# ADC_channel.net
KiCad netlist of a schematic drawn in Altium Designer
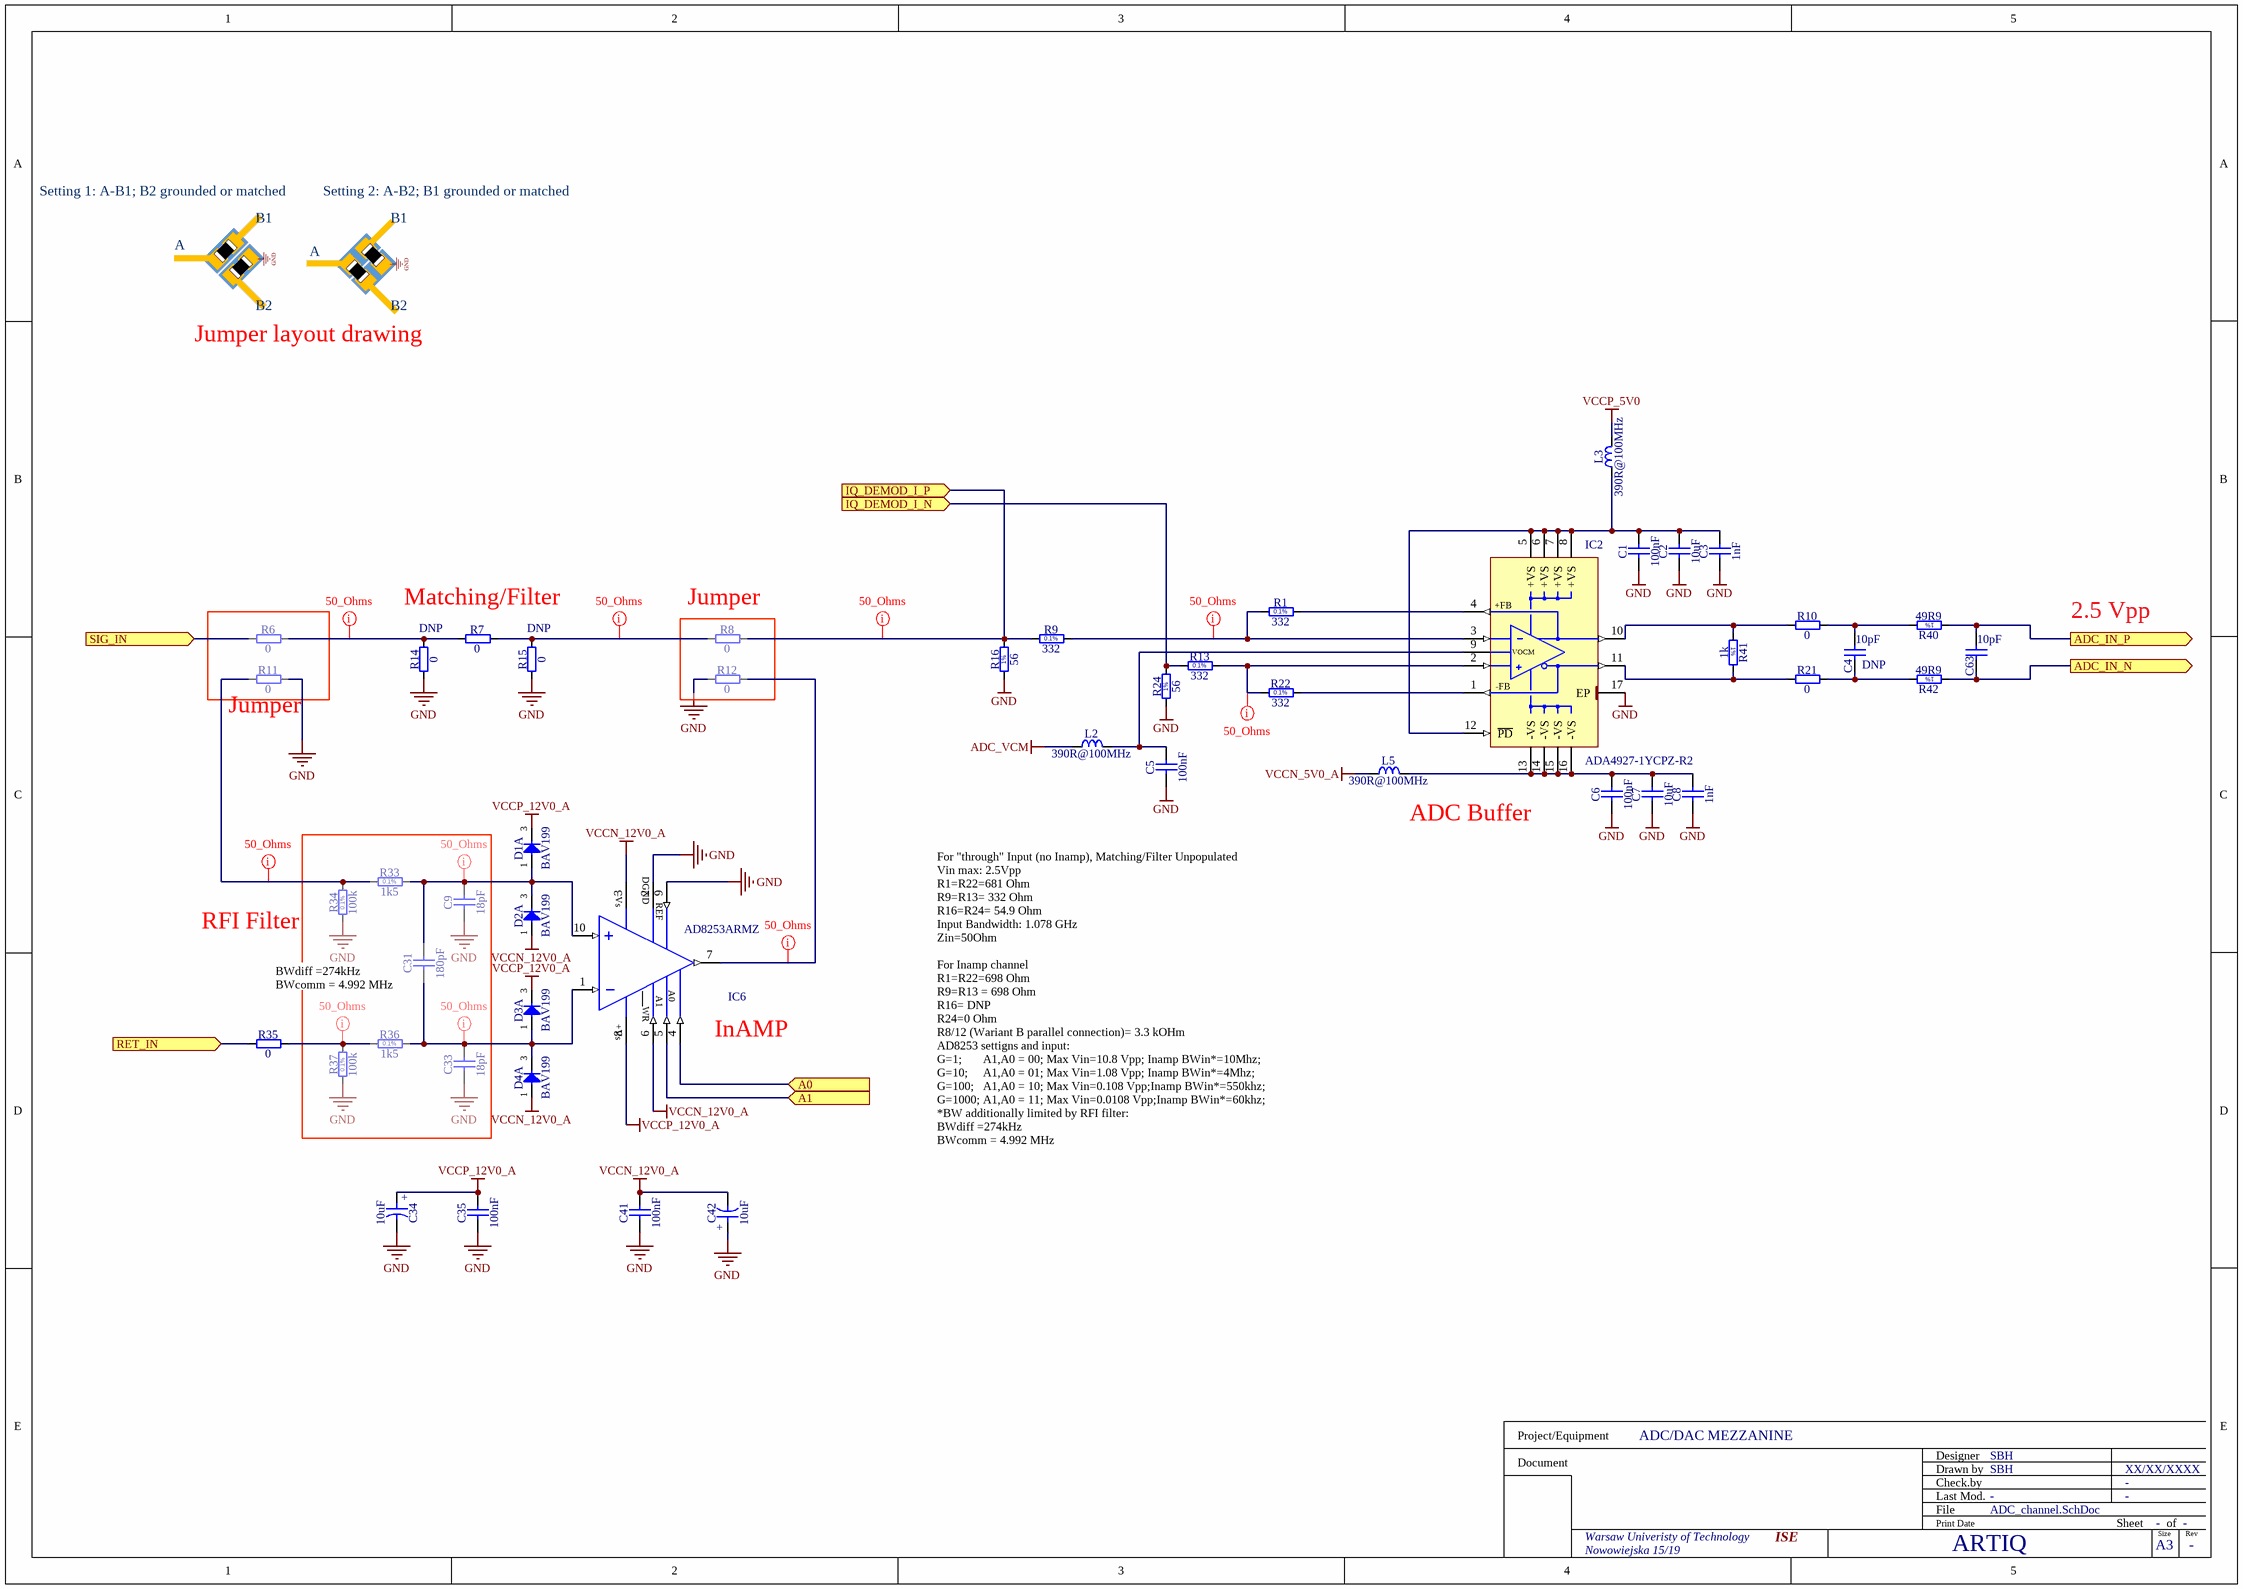
[diagram p0: ADC_channel.SchDoc]

(export (version "E")
  (design (tool "Eeschema 10.0.6"))
  (components
    (comp (ref "C1")
      (value "100nF")
      (footprint "CAPC1005X55N")
      (description "Non-polarised capacitor")
      (fields
        (field (name "PART NUMBER") "CC0402_100NF_16V_10%_X5R")
        (field (name "VOLTAGE") "16V")
        (field (name "AUTHOR") "CERN DEM JLC")
      )
      (libsource (lib "Capacitors") (part "Capacitor - non polarized"))
    )
    (comp (ref "C2")
      (value "10uF")
      (footprint "CAPC1608X87N")
      (description "Non-polarised capacitor")
      (fields
        (field (name "PART NUMBER") "CC0603_10UF_6.3V_20%_X5R")
        (field (name "VOLTAGE") "6.3V")
        (field (name "AUTHOR") "CERN DEM JLC")
      )
      (libsource (lib "Capacitors") (part "Capacitor - non polarized"))
    )
    (comp (ref "C3")
      (value "1nF")
      (footprint "CAPC1005X55N")
      (description "Non-polarised capacitor")
      (fields
        (field (name "PART NUMBER") "CC0402_1NF_50V_10%_X7R")
        (field (name "VOLTAGE") "50V")
        (field (name "AUTHOR") "CERN DEM JLC")
      )
      (libsource (lib "Capacitors") (part "Capacitor - non polarized"))
    )
    (comp (ref "C4")
      (value "10pF")
      (footprint "CAPC1608X87N")
      (description "Non-polarised capacitor")
      (fields
        (field (name "PART NUMBER") "CC0603_10PF_50V_5%_NP0")
        (field (name "VOLTAGE") "50V")
        (field (name "MOUNTED") "DNP")
        (field (name "AUTHOR") "CERN DEM JLC")
      )
      (libsource (lib "Capacitors") (part "Capacitor - non polarized"))
    )
    (comp (ref "C5")
      (value "100nF")
      (footprint "CAPC1005X55N")
      (description "Non-polarised capacitor")
      (fields
        (field (name "PART NUMBER") "CC0402_100NF_16V_10%_X5R")
        (field (name "VOLTAGE") "16V")
        (field (name "AUTHOR") "CERN DEM JLC")
      )
      (libsource (lib "Capacitors") (part "Capacitor - non polarized"))
    )
    (comp (ref "C6")
      (value "100nF")
      (footprint "CAPC1005X55N")
      (description "Non-polarised capacitor")
      (fields
        (field (name "PART NUMBER") "CC0402_100NF_16V_10%_X5R")
        (field (name "VOLTAGE") "16V")
        (field (name "AUTHOR") "CERN DEM JLC")
      )
      (libsource (lib "Capacitors") (part "Capacitor - non polarized"))
    )
    (comp (ref "C7")
      (value "10uF")
      (footprint "CAPC1608X87N")
      (description "Non-polarised capacitor")
      (fields
        (field (name "PART NUMBER") "CC0603_10UF_6.3V_20%_X5R")
        (field (name "VOLTAGE") "6.3V")
        (field (name "AUTHOR") "CERN DEM JLC")
      )
      (libsource (lib "Capacitors") (part "Capacitor - non polarized"))
    )
    (comp (ref "C8")
      (value "1nF")
      (footprint "CAPC1005X55N")
      (description "Non-polarised capacitor")
      (fields
        (field (name "PART NUMBER") "CC0402_1NF_50V_10%_X7R")
        (field (name "VOLTAGE") "50V")
        (field (name "AUTHOR") "CERN DEM JLC")
      )
      (libsource (lib "Capacitors") (part "Capacitor - non polarized"))
    )
    (comp (ref "C9")
      (value "18pF")
      (footprint "CAPC1005X55N")
      (description "Non-polarised capacitor")
      (fields
        (field (name "PART NUMBER") "CC0402_18PF_50V_5%_C0G")
        (field (name "VOLTAGE") "50V")
        (field (name "AUTHOR") "CERN DEM JLC")
      )
      (libsource (lib "Capacitors") (part "Capacitor - non polarized"))
    )
    (comp (ref "C31")
      (value "180pF")
      (footprint "CAPC3216X140N")
      (description "Non-polarised capacitor")
      (fields
        (field (name "PART NUMBER") "CC1206_180PF_50V_5%_NP0")
        (field (name "VOLTAGE") "50V")
        (field (name "AUTHOR") "CERN DEM JLC")
      )
      (libsource (lib "Capacitors") (part "Capacitor - non polarized"))
    )
    (comp (ref "C33")
      (value "18pF")
      (footprint "CAPC1005X55N")
      (description "Non-polarised capacitor")
      (fields
        (field (name "PART NUMBER") "CC0402_18PF_50V_5%_C0G")
        (field (name "VOLTAGE") "50V")
        (field (name "AUTHOR") "CERN DEM JLC")
      )
      (libsource (lib "Capacitors") (part "Capacitor - non polarized"))
    )
    (comp (ref "C34")
      (value "10uF")
      (footprint "CAPMP3216X180N")
      (description "Polarised capacitor")
      (fields
        (field (name "PART NUMBER") "CTE3216-18_10UF_16V_20%_AVX_TCJ")
        (field (name "VOLTAGE") "16V")
        (field (name "AUTHOR") "CERN DEM JLC")
      )
      (libsource (lib "Capacitors") (part "Capacitor - polarized"))
    )
    (comp (ref "C35")
      (value "100nF")
      (footprint "CAPC1005X55N")
      (description "Non-polarised capacitor")
      (fields
        (field (name "PART NUMBER") "CC0402_100NF_16V_10%_X7R")
        (field (name "VOLTAGE") "16V")
        (field (name "AUTHOR") "CERN DEM JLC")
      )
      (libsource (lib "Capacitors") (part "Capacitor - non polarized"))
    )
    (comp (ref "C41")
      (value "100nF")
      (footprint "CAPC1005X55N")
      (description "Non-polarised capacitor")
      (fields
        (field (name "PART NUMBER") "CC0402_100NF_16V_10%_X7R")
        (field (name "VOLTAGE") "16V")
        (field (name "AUTHOR") "CERN DEM JLC")
      )
      (libsource (lib "Capacitors") (part "Capacitor - non polarized"))
    )
    (comp (ref "C42")
      (value "10uF")
      (footprint "CAPMP3216X180N")
      (description "Polarised capacitor")
      (fields
        (field (name "PART NUMBER") "CTE3216-18_10UF_16V_20%_AVX_TCJ")
        (field (name "VOLTAGE") "16V")
        (field (name "AUTHOR") "CERN DEM JLC")
      )
      (libsource (lib "Capacitors") (part "Capacitor - polarized"))
    )
    (comp (ref "C63")
      (value "10pF")
      (footprint "CAPC1608X87N")
      (description "Non-polarised capacitor")
      (fields
        (field (name "PART NUMBER") "CC0603_10PF_50V_5%_NP0")
        (field (name "VOLTAGE") "50V")
        (field (name "AUTHOR") "CERN DEM JLC")
      )
      (libsource (lib "Capacitors") (part "Capacitor - non polarized"))
    )
    (comp (ref "D1")
      (value "BAV199")
      (footprint "SOT95P240X110-3N")
      (description "Serial Diode")
      (fields
        (field (name "VOLTAGE") "75V")
        (field (name "POWER") "250mW")
        (field (name "AUTHOR") "CERN DEM JMW")
      )
      (libsource (lib "ICs And Semiconductors") (part "Diode x2 A1C3_A3C2"))
    )
    (comp (ref "D2")
      (value "BAV199")
      (footprint "SOT95P240X110-3N")
      (description "Serial Diode")
      (fields
        (field (name "VOLTAGE") "75V")
        (field (name "POWER") "250mW")
        (field (name "AUTHOR") "CERN DEM JMW")
      )
      (libsource (lib "ICs And Semiconductors") (part "Diode x2 A1C3_A3C2"))
    )
    (comp (ref "D3")
      (value "BAV199")
      (footprint "SOT95P240X110-3N")
      (description "Serial Diode")
      (fields
        (field (name "VOLTAGE") "75V")
        (field (name "POWER") "250mW")
        (field (name "AUTHOR") "CERN DEM JMW")
      )
      (libsource (lib "ICs And Semiconductors") (part "Diode x2 A1C3_A3C2"))
    )
    (comp (ref "D4")
      (value "BAV199")
      (footprint "SOT95P240X110-3N")
      (description "Serial Diode")
      (fields
        (field (name "VOLTAGE") "75V")
        (field (name "POWER") "250mW")
        (field (name "AUTHOR") "CERN DEM JMW")
      )
      (libsource (lib "ICs And Semiconductors") (part "Diode x2 A1C3_A3C2"))
    )
    (comp (ref "IC2")
      (value "ADA4927-1YCPZ-R2")
      (footprint "QFN50P300X300X100-17N-S145")
      (description "Ultralow Distortion Current Feedback Differential ADC Driver")
      (fields (field (name "MANUFACTURER") "ANALOG DEVICES") (field (name "AUTHOR") "CERN DEM JLC"))
      (libsource (lib "ICs And Semiconductors") (part "ADA4927-1"))
    )
    (comp (ref "IC6")
      (value "AD8253ARMZ")
      (footprint "SOP50P490X110-10N")
      (description "10MHz, 20V/us, G= 1, 10, 100, 1000 iCMOS Programmable Gain Instrumentation Amplifier")
      (fields (field (name "MANUFACTURER") "ANALOG DEVICES") (field (name "AUTHOR") "CERN DEM JLC"))
      (libsource (lib "ICs And Semiconductors") (part "AD8253"))
    )
    (comp (ref "L2")
      (value "390R@100MHz")
      (footprint "INDC1608X95N")
      (description "Inductor")
      (fields
        (field (name "PART NUMBER") "IND0603_TDK_MPZ1608R391A")
        (field (name "POWER") "1.2A")
        (field (name "AUTHOR") "CERN DEM JLC")
      )
      (libsource (lib "") (part "Inductor_1"))
    )
    (comp (ref "L3")
      (value "390R@100MHz")
      (footprint "INDC1608X95N")
      (description "Inductor")
      (fields
        (field (name "PART NUMBER") "IND0603_TDK_MPZ1608R391A")
        (field (name "POWER") "1.2A")
        (field (name "AUTHOR") "CERN DEM JLC")
      )
      (libsource (lib "Inductors & Transformers") (part "Inductor"))
    )
    (comp (ref "L5")
      (value "390R@100MHz")
      (footprint "INDC1608X95N")
      (description "Inductor")
      (fields
        (field (name "PART NUMBER") "IND0603_TDK_MPZ1608R391A")
        (field (name "POWER") "1.2A")
        (field (name "AUTHOR") "CERN DEM JLC")
      )
      (libsource (lib "") (part "Inductor_1"))
    )
    (comp (ref "R1")
      (value "332")
      (footprint "RESC1608X55N")
      (description "Resistor - 0.1%")
      (fields
        (field (name "PART NUMBER") "R0603_332R_0.1%_0.063W_10PPM")
        (field (name "POWER") "0.063W")
        (field (name "AUTHOR") "CERN DEM JLC")
      )
      (libsource (lib "Resistors") (part "Resistor - 0.1%"))
    )
    (comp (ref "R6")
      (value "0")
      (footprint "RESC1005X40N")
      (description "Resistor")
      (fields
        (field (name "PART NUMBER") "R0402_0R_JUMPER")
        (field (name "MANUFACTURER") "GENERIC")
        (field (name "AUTHOR") "CERN DEM JLC")
      )
      (libsource (lib "Resistors") (part "Resistor"))
    )
    (comp (ref "R7")
      (value "0")
      (footprint "RESC1005X40N")
      (description "Resistor")
      (fields
        (field (name "PART NUMBER") "R0402_0R_JUMPER")
        (field (name "MANUFACTURER") "GENERIC")
        (field (name "AUTHOR") "CERN DEM JLC")
      )
      (libsource (lib "Resistors") (part "Resistor"))
    )
    (comp (ref "R8")
      (value "0")
      (footprint "RESC1005X40N")
      (description "Resistor")
      (fields
        (field (name "PART NUMBER") "R0402_0R_JUMPER")
        (field (name "MANUFACTURER") "GENERIC")
        (field (name "AUTHOR") "CERN DEM JLC")
      )
      (libsource (lib "Resistors") (part "Resistor"))
    )
    (comp (ref "R9")
      (value "332")
      (footprint "RESC1608X55N")
      (description "Resistor - 0.1%")
      (fields
        (field (name "PART NUMBER") "R0603_332R_0.1%_0.063W_10PPM")
        (field (name "POWER") "0.063W")
        (field (name "AUTHOR") "CERN DEM JLC")
      )
      (libsource (lib "Resistors") (part "Resistor - 0.1%"))
    )
    (comp (ref "R10")
      (value "0")
      (footprint "RESC1005X40N")
      (description "Resistor")
      (fields
        (field (name "PART NUMBER") "R0402_0R_JUMPER")
        (field (name "MANUFACTURER") "GENERIC")
        (field (name "AUTHOR") "CERN DEM JLC")
      )
      (libsource (lib "Resistors") (part "Resistor"))
    )
    (comp (ref "R11")
      (value "0")
      (footprint "RESC1005X40N")
      (description "Resistor")
      (fields
        (field (name "PART NUMBER") "R0402_0R_JUMPER")
        (field (name "MANUFACTURER") "GENERIC")
        (field (name "AUTHOR") "CERN DEM JLC")
      )
      (libsource (lib "Resistors") (part "Resistor"))
    )
    (comp (ref "R12")
      (value "0")
      (footprint "RESC1005X40N")
      (description "Resistor")
      (fields
        (field (name "PART NUMBER") "R0402_0R_JUMPER")
        (field (name "MANUFACTURER") "GENERIC")
        (field (name "AUTHOR") "CERN DEM JLC")
      )
      (libsource (lib "Resistors") (part "Resistor"))
    )
    (comp (ref "R13")
      (value "332")
      (footprint "RESC1608X55N")
      (description "Resistor - 0.1%")
      (fields
        (field (name "PART NUMBER") "R0603_332R_0.1%_0.063W_10PPM")
        (field (name "POWER") "0.063W")
        (field (name "AUTHOR") "CERN DEM JLC")
      )
      (libsource (lib "Resistors") (part "Resistor - 0.1%"))
    )
    (comp (ref "R14")
      (value "0")
      (footprint "RESC1005X40N")
      (description "Resistor")
      (fields
        (field (name "PART NUMBER") "R0402_0R_JUMPER")
        (field (name "MANUFACTURER") "GENERIC")
        (field (name "MOUNTED") "DNP")
        (field (name "AUTHOR") "CERN DEM JLC")
      )
      (libsource (lib "Resistors") (part "Resistor"))
    )
    (comp (ref "R15")
      (value "0")
      (footprint "RESC1005X40N")
      (description "Resistor")
      (fields
        (field (name "PART NUMBER") "R0402_0R_JUMPER")
        (field (name "MANUFACTURER") "GENERIC")
        (field (name "MOUNTED") "DNP")
        (field (name "AUTHOR") "CERN DEM JLC")
      )
      (libsource (lib "Resistors") (part "Resistor"))
    )
    (comp (ref "R16")
      (value "56")
      (footprint "RESC1005X40N")
      (description "Resistor - 1%")
      (fields
        (field (name "PART NUMBER") "R0402_56R_1%_0.0625W_100PPM")
        (field (name "POWER") "0.0625W")
        (field (name "AUTHOR") "CERN DEM JLC")
      )
      (libsource (lib "Resistors") (part "Resistor - 1%"))
    )
    (comp (ref "R21")
      (value "0")
      (footprint "RESC1005X40N")
      (description "Resistor")
      (fields
        (field (name "PART NUMBER") "R0402_0R_JUMPER")
        (field (name "MANUFACTURER") "GENERIC")
        (field (name "AUTHOR") "CERN DEM JLC")
      )
      (libsource (lib "Resistors") (part "Resistor"))
    )
    (comp (ref "R22")
      (value "332")
      (footprint "RESC1608X55N")
      (description "Resistor - 0.1%")
      (fields
        (field (name "PART NUMBER") "R0603_332R_0.1%_0.063W_10PPM")
        (field (name "POWER") "0.063W")
        (field (name "AUTHOR") "CERN DEM JLC")
      )
      (libsource (lib "Resistors") (part "Resistor - 0.1%"))
    )
    (comp (ref "R24")
      (value "56")
      (footprint "RESC1005X40N")
      (description "Resistor - 1%")
      (fields
        (field (name "PART NUMBER") "R0402_56R_1%_0.0625W_100PPM")
        (field (name "POWER") "0.0625W")
        (field (name "AUTHOR") "CERN DEM JLC")
      )
      (libsource (lib "Resistors") (part "Resistor - 1%"))
    )
    (comp (ref "R33")
      (value "1k5")
      (footprint "RESC1608X55N")
      (description "Resistor - 0.1%")
      (fields
        (field (name "PART NUMBER") "R0603_1K5_0.1%_0.063W_10PPM")
        (field (name "POWER") "0.063W")
        (field (name "AUTHOR") "CERN DEM JLC")
      )
      (libsource (lib "Resistors") (part "Resistor - 0.1%"))
    )
    (comp (ref "R34")
      (value "100k")
      (footprint "RESC1005X35N")
      (description "Resistor - 0.1%")
      (fields
        (field (name "PART NUMBER") "R0402_100K_0.1%_0.063W_25PPM")
        (field (name "POWER") "0.063W")
        (field (name "AUTHOR") "CERN DEM JMW")
      )
      (libsource (lib "Resistors") (part "Resistor - 0.1%"))
    )
    (comp (ref "R35")
      (value "0")
      (footprint "RESC1005X40N")
      (description "Resistor")
      (fields
        (field (name "PART NUMBER") "R0402_0R_JUMPER")
        (field (name "MANUFACTURER") "GENERIC")
        (field (name "AUTHOR") "CERN DEM JLC")
      )
      (libsource (lib "Resistors") (part "Resistor"))
    )
    (comp (ref "R36")
      (value "1k5")
      (footprint "RESC1608X55N")
      (description "Resistor - 0.1%")
      (fields
        (field (name "PART NUMBER") "R0603_1K5_0.1%_0.063W_10PPM")
        (field (name "POWER") "0.063W")
        (field (name "AUTHOR") "CERN DEM JLC")
      )
      (libsource (lib "Resistors") (part "Resistor - 0.1%"))
    )
    (comp (ref "R37")
      (value "100k")
      (footprint "RESC1005X35N")
      (description "Resistor - 0.1%")
      (fields
        (field (name "PART NUMBER") "R0402_100K_0.1%_0.063W_25PPM")
        (field (name "POWER") "0.063W")
        (field (name "AUTHOR") "CERN DEM JMW")
      )
      (libsource (lib "Resistors") (part "Resistor - 0.1%"))
    )
    (comp (ref "R40")
      (value "49R9")
      (footprint "RESC1005X40N")
      (description "Resistor - 1%")
      (fields
        (field (name "PART NUMBER") "R0402_49R9_1%_0.0625W_100PPM")
        (field (name "POWER") "0.0625W")
        (field (name "AUTHOR") "CERN DEM JLC")
      )
      (libsource (lib "Resistors") (part "Resistor - 1%"))
    )
    (comp (ref "R41")
      (value "1k")
      (footprint "RESC1005X40N")
      (description "Resistor - 1%")
      (fields
        (field (name "PART NUMBER") "R0402_1K_1%_0.0625W_100PPM")
        (field (name "POWER") "0.0625W")
        (field (name "AUTHOR") "CERN DEM JLC")
      )
      (libsource (lib "Resistors") (part "Resistor - 1%"))
    )
    (comp (ref "R42")
      (value "49R9")
      (footprint "RESC1005X40N")
      (description "Resistor - 1%")
      (fields
        (field (name "PART NUMBER") "R0402_49R9_1%_0.0625W_100PPM")
        (field (name "POWER") "0.0625W")
        (field (name "AUTHOR") "CERN DEM JLC")
      )
      (libsource (lib "Resistors") (part "Resistor - 1%"))
    )
  )
  (nets
    (net (code "1") (name "/A0") (class "Default")
      (node (ref "IC6") (pin "4") (pinfunction "A0_4") (pintype "input"))
    )
    (net (code "2") (name "/A1") (class "Default")
      (node (ref "IC6") (pin "5") (pinfunction "A1_5") (pintype "input"))
    )
    (net (code "3") (name "/ADC_IN_N") (class "Default")
      (node (ref "C63") (pin "1") (pinfunction "1_1") (pintype "passive"))
      (node (ref "R42") (pin "1") (pinfunction "1_1") (pintype "passive"))
    )
    (net (code "4") (name "/ADC_IN_P") (class "Default")
      (node (ref "C63") (pin "2") (pinfunction "2_2") (pintype "passive"))
      (node (ref "R40") (pin "1") (pinfunction "1_1") (pintype "passive"))
    )
    (net (code "5") (name "/IQ_DEMOD_I_N") (class "Default")
      (node (ref "R13") (pin "1") (pinfunction "1_1") (pintype "passive"))
      (node (ref "R24") (pin "2") (pinfunction "2_2") (pintype "passive"))
    )
    (net (code "6") (name "/IQ_DEMOD_I_P") (class "Default")
      (node (ref "R16") (pin "2") (pinfunction "2_2") (pintype "passive"))
      (node (ref "R8") (pin "1") (pinfunction "1_1") (pintype "passive"))
      (node (ref "R9") (pin "1") (pinfunction "1_1") (pintype "passive"))
    )
    (net (code "7") (name "/RET_IN") (class "Default")
      (node (ref "R35") (pin "1") (pinfunction "1_1") (pintype "passive"))
    )
    (net (code "8") (name "/SIG_IN") (class "Default")
      (node (ref "R6") (pin "1") (pinfunction "1_1") (pintype "passive"))
    )
    (net (code "9") (name "ADC_VCM") (class "Default")
      (node (ref "L2") (pin "1") (pinfunction "1_1") (pintype "passive"))
    )
    (net (code "10") (name "GND") (class "Default")
      (node (ref "C1") (pin "1") (pinfunction "1_1") (pintype "passive"))
      (node (ref "C2") (pin "1") (pinfunction "1_1") (pintype "passive"))
      (node (ref "C3") (pin "1") (pinfunction "1_1") (pintype "passive"))
      (node (ref "C33") (pin "1") (pinfunction "1_1") (pintype "passive"))
      (node (ref "C34") (pin "2") (pinfunction "2_2") (pintype "passive"))
      (node (ref "C35") (pin "1") (pinfunction "1_1") (pintype "passive"))
      (node (ref "C41") (pin "1") (pinfunction "1_1") (pintype "passive"))
      (node (ref "C42") (pin "1") (pinfunction "1_1") (pintype "passive"))
      (node (ref "C5") (pin "1") (pinfunction "1_1") (pintype "passive"))
      (node (ref "C6") (pin "1") (pinfunction "1_1") (pintype "passive"))
      (node (ref "C7") (pin "1") (pinfunction "1_1") (pintype "passive"))
      (node (ref "C8") (pin "1") (pinfunction "1_1") (pintype "passive"))
      (node (ref "C9") (pin "1") (pinfunction "1_1") (pintype "passive"))
      (node (ref "IC2") (pin "17") (pinfunction "EP_17") (pintype "power_in"))
      (node (ref "IC6") (pin "2") (pinfunction "DGND_2") (pintype "power_in"))
      (node (ref "IC6") (pin "9") (pinfunction "REF_9") (pintype "input"))
      (node (ref "R11") (pin "2") (pinfunction "2_2") (pintype "passive"))
      (node (ref "R12") (pin "2") (pinfunction "2_2") (pintype "passive"))
      (node (ref "R14") (pin "1") (pinfunction "1_1") (pintype "passive"))
      (node (ref "R15") (pin "1") (pinfunction "1_1") (pintype "passive"))
      (node (ref "R16") (pin "1") (pinfunction "1_1") (pintype "passive"))
      (node (ref "R24") (pin "1") (pinfunction "1_1") (pintype "passive"))
      (node (ref "R34") (pin "1") (pinfunction "1_1") (pintype "passive"))
      (node (ref "R37") (pin "1") (pinfunction "1_1") (pintype "passive"))
    )
    (net (code "11") (name "Net-(C4-Pad1)") (class "Default")
      (node (ref "C4") (pin "1") (pinfunction "1_1") (pintype "passive"))
      (node (ref "R21") (pin "2") (pinfunction "2_2") (pintype "passive"))
      (node (ref "R42") (pin "2") (pinfunction "2_2") (pintype "passive"))
    )
    (net (code "12") (name "Net-(C4-Pad2)") (class "Default")
      (node (ref "C4") (pin "2") (pinfunction "2_2") (pintype "passive"))
      (node (ref "R10") (pin "2") (pinfunction "2_2") (pintype "passive"))
      (node (ref "R40") (pin "2") (pinfunction "2_2") (pintype "passive"))
    )
    (net (code "13") (name "Net-(C6-Pad2)") (class "Default")
      (node (ref "C6") (pin "2") (pinfunction "2_2") (pintype "passive"))
      (node (ref "C7") (pin "2") (pinfunction "2_2") (pintype "passive"))
      (node (ref "C8") (pin "2") (pinfunction "2_2") (pintype "passive"))
      (node (ref "IC2") (pin "13") (pinfunction "-VS_13") (pintype "power_in"))
      (node (ref "IC2") (pin "14") (pinfunction "-VS_14") (pintype "power_in"))
      (node (ref "IC2") (pin "15") (pinfunction "-VS_15") (pintype "power_in"))
      (node (ref "IC2") (pin "16") (pinfunction "-VS_16") (pintype "power_in"))
      (node (ref "L5") (pin "2") (pinfunction "2_2") (pintype "passive"))
    )
    (net (code "14") (name "Net-(D1A-A)") (class "Default")
      (node (ref "C31") (pin "2") (pinfunction "2_2") (pintype "passive"))
      (node (ref "C9") (pin "2") (pinfunction "2_2") (pintype "passive"))
      (node (ref "D1") (pin "1") (pinfunction "A_1") (pintype "passive"))
      (node (ref "D2") (pin "3") (pinfunction "COMAC_3") (pintype "passive"))
      (node (ref "IC6") (pin "10") (pinfunction "+IN_10") (pintype "input"))
      (node (ref "R33") (pin "2") (pinfunction "2_2") (pintype "passive"))
    )
    (net (code "15") (name "Net-(D3A-A)") (class "Default")
      (node (ref "C31") (pin "1") (pinfunction "1_1") (pintype "passive"))
      (node (ref "C33") (pin "2") (pinfunction "2_2") (pintype "passive"))
      (node (ref "D3") (pin "1") (pinfunction "A_1") (pintype "passive"))
      (node (ref "D4") (pin "3") (pinfunction "COMAC_3") (pintype "passive"))
      (node (ref "IC6") (pin "1") (pinfunction "-IN_1") (pintype "input"))
      (node (ref "R36") (pin "2") (pinfunction "2_2") (pintype "passive"))
    )
    (net (code "16") (name "Net-(IC2-+FB)") (class "Default")
      (node (ref "IC2") (pin "4") (pinfunction "+FB_4") (pintype "output"))
      (node (ref "R1") (pin "2") (pinfunction "2_2") (pintype "passive"))
    )
    (net (code "17") (name "Net-(IC2-+IN)") (class "Default")
      (node (ref "IC2") (pin "2") (pinfunction "+IN_2") (pintype "input"))
      (node (ref "R13") (pin "2") (pinfunction "2_2") (pintype "passive"))
      (node (ref "R22") (pin "1") (pinfunction "1_1") (pintype "passive"))
    )
    (net (code "18") (name "Net-(IC2-+OUT)") (class "Default")
      (node (ref "IC2") (pin "10") (pinfunction "+OUT_10") (pintype "output"))
      (node (ref "R10") (pin "1") (pinfunction "1_1") (pintype "passive"))
      (node (ref "R41") (pin "1") (pinfunction "1_1") (pintype "passive"))
    )
    (net (code "19") (name "Net-(IC2--FB)") (class "Default")
      (node (ref "IC2") (pin "1") (pinfunction "-FB_1") (pintype "output"))
      (node (ref "R22") (pin "2") (pinfunction "2_2") (pintype "passive"))
    )
    (net (code "20") (name "Net-(IC2--IN)") (class "Default")
      (node (ref "IC2") (pin "3") (pinfunction "-IN_3") (pintype "input"))
      (node (ref "R1") (pin "1") (pinfunction "1_1") (pintype "passive"))
      (node (ref "R9") (pin "2") (pinfunction "2_2") (pintype "passive"))
    )
    (net (code "21") (name "Net-(IC2--OUT)") (class "Default")
      (node (ref "IC2") (pin "11") (pinfunction "-OUT_11") (pintype "output"))
      (node (ref "R21") (pin "1") (pinfunction "1_1") (pintype "passive"))
      (node (ref "R41") (pin "2") (pinfunction "2_2") (pintype "passive"))
    )
    (net (code "22") (name "Net-(IC2-VOCM)") (class "Default")
      (node (ref "C5") (pin "2") (pinfunction "2_2") (pintype "passive"))
      (node (ref "IC2") (pin "9") (pinfunction "VOCM_9") (pintype "passive"))
      (node (ref "L2") (pin "2") (pinfunction "2_2") (pintype "passive"))
    )
    (net (code "23") (name "Net-(IC2-~{PD})") (class "Default")
      (node (ref "C1") (pin "2") (pinfunction "2_2") (pintype "passive"))
      (node (ref "C2") (pin "2") (pinfunction "2_2") (pintype "passive"))
      (node (ref "C3") (pin "2") (pinfunction "2_2") (pintype "passive"))
      (node (ref "IC2") (pin "12") (pinfunction "~{PD}_12") (pintype "input"))
      (node (ref "IC2") (pin "5") (pinfunction "+VS_5") (pintype "power_in"))
      (node (ref "IC2") (pin "6") (pinfunction "+VS_6") (pintype "power_in"))
      (node (ref "IC2") (pin "7") (pinfunction "+VS_7") (pintype "power_in"))
      (node (ref "IC2") (pin "8") (pinfunction "+VS_8") (pintype "power_in"))
      (node (ref "L3") (pin "1") (pinfunction "1_1") (pintype "passive"))
    )
    (net (code "24") (name "Net-(IC6-OUT)") (class "Default")
      (node (ref "IC6") (pin "7") (pinfunction "OUT_7") (pintype "output"))
      (node (ref "R12") (pin "1") (pinfunction "1_1") (pintype "passive"))
    )
    (net (code "25") (name "Net-(R11-Pad1)") (class "Default")
      (node (ref "R11") (pin "1") (pinfunction "1_1") (pintype "passive"))
      (node (ref "R33") (pin "1") (pinfunction "1_1") (pintype "passive"))
      (node (ref "R34") (pin "2") (pinfunction "2_2") (pintype "passive"))
    )
    (net (code "26") (name "Net-(R14-Pad2)") (class "Default")
      (node (ref "R14") (pin "2") (pinfunction "2_2") (pintype "passive"))
      (node (ref "R6") (pin "2") (pinfunction "2_2") (pintype "passive"))
      (node (ref "R7") (pin "1") (pinfunction "1_1") (pintype "passive"))
    )
    (net (code "27") (name "Net-(R15-Pad2)") (class "Default")
      (node (ref "R15") (pin "2") (pinfunction "2_2") (pintype "passive"))
      (node (ref "R7") (pin "2") (pinfunction "2_2") (pintype "passive"))
      (node (ref "R8") (pin "2") (pinfunction "2_2") (pintype "passive"))
    )
    (net (code "28") (name "Net-(R35-Pad2)") (class "Default")
      (node (ref "R35") (pin "2") (pinfunction "2_2") (pintype "passive"))
      (node (ref "R36") (pin "1") (pinfunction "1_1") (pintype "passive"))
      (node (ref "R37") (pin "2") (pinfunction "2_2") (pintype "passive"))
    )
    (net (code "29") (name "VCCN_5V0_A") (class "Default")
      (node (ref "L5") (pin "1") (pinfunction "1_1") (pintype "passive"))
    )
    (net (code "30") (name "VCCN_12V0_A") (class "Default")
      (node (ref "C41") (pin "2") (pinfunction "2_2") (pintype "passive"))
      (node (ref "C42") (pin "2") (pinfunction "2_2") (pintype "passive"))
      (node (ref "D2") (pin "1") (pinfunction "A_1") (pintype "passive"))
      (node (ref "D4") (pin "1") (pinfunction "A_1") (pintype "passive"))
      (node (ref "IC6") (pin "3") (pinfunction "-VS_3") (pintype "power_in"))
      (node (ref "IC6") (pin "6") (pinfunction "~{WR}_6") (pintype "input"))
    )
    (net (code "31") (name "VCCP_5V0") (class "Default")
      (node (ref "L3") (pin "2") (pinfunction "2_2") (pintype "passive"))
    )
    (net (code "32") (name "VCCP_12V0_A") (class "Default")
      (node (ref "C34") (pin "1") (pinfunction "1_1") (pintype "passive"))
      (node (ref "C35") (pin "2") (pinfunction "2_2") (pintype "passive"))
      (node (ref "D1") (pin "3") (pinfunction "COMAC_3") (pintype "passive"))
      (node (ref "D3") (pin "3") (pinfunction "COMAC_3") (pintype "passive"))
      (node (ref "IC6") (pin "8") (pinfunction "+VS_8") (pintype "power_in"))
    )
  )
)
